# OLED_V3_1.net
KiCad netlist of a schematic drawn in Altium Designer
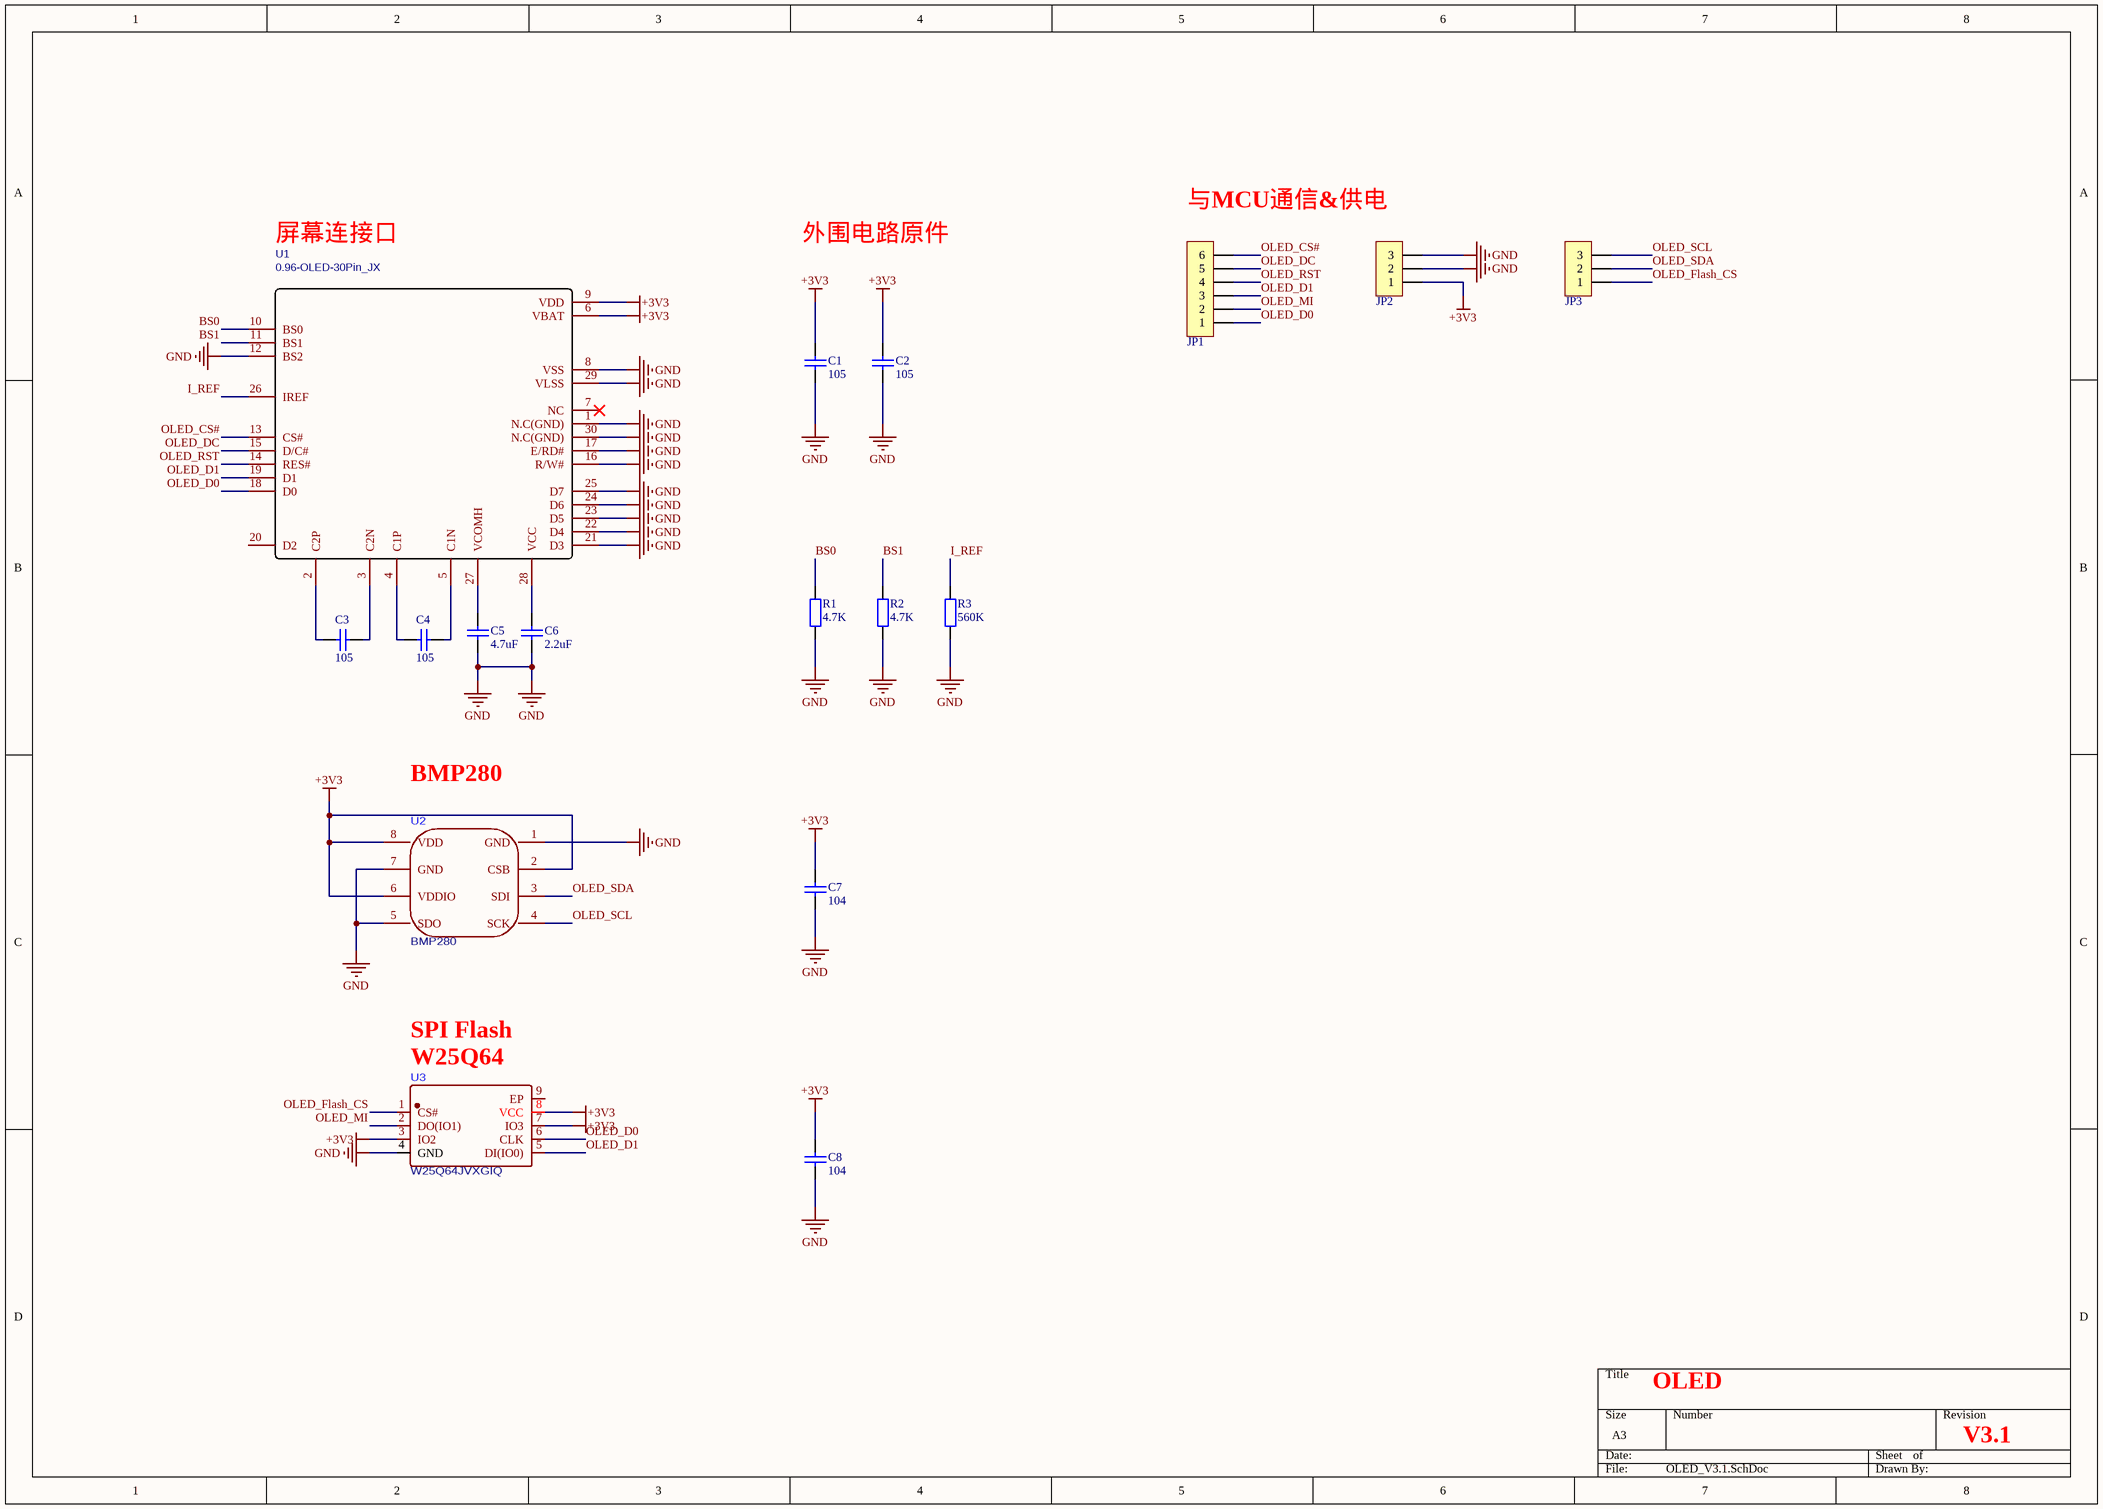
[diagram p0: OLED_V3.1.SchDoc]

(export (version "E")
  (design (tool "Eeschema 10.0.6"))
  (components
    (comp (ref "C1")
      (value "105")
      (footprint "C0603_M")
      (description "贴片电容/MLCC电容")
      (libsource (lib "R-L-C-FUSE-XTAL-FB-RX") (part "C"))
    )
    (comp (ref "C2")
      (value "105")
      (footprint "C0603_M")
      (description "贴片电容/MLCC电容")
      (libsource (lib "R-L-C-FUSE-XTAL-FB-RX") (part "C"))
    )
    (comp (ref "C3")
      (value "105")
      (footprint "C0603_M")
      (description "贴片电容/MLCC电容")
      (libsource (lib "R-L-C-FUSE-XTAL-FB-RX") (part "C"))
    )
    (comp (ref "C4")
      (value "105")
      (footprint "C0603_M")
      (description "贴片电容/MLCC电容")
      (libsource (lib "R-L-C-FUSE-XTAL-FB-RX") (part "C"))
    )
    (comp (ref "C5")
      (value "4.7uF")
      (footprint "C0603_M")
      (description "贴片电容/MLCC电容")
      (libsource (lib "R-L-C-FUSE-XTAL-FB-RX") (part "C"))
    )
    (comp (ref "C6")
      (value "2.2uF")
      (footprint "C0603_M")
      (description "贴片电容/MLCC电容")
      (libsource (lib "R-L-C-FUSE-XTAL-FB-RX") (part "C"))
    )
    (comp (ref "C7")
      (value "104")
      (footprint "C0603_M")
      (description "贴片电容/MLCC电容")
      (libsource (lib "R-L-C-FUSE-XTAL-FB-RX") (part "C"))
    )
    (comp (ref "C8")
      (value "104")
      (footprint "C0603_M")
      (description "贴片电容/MLCC电容")
      (libsource (lib "R-L-C-FUSE-XTAL-FB-RX") (part "C"))
    )
    (comp (ref "JP1")
      (value "HDR-1X6")
      (footprint "HDR-1X6")
      (description "6P接插件")
      (fields (field (name "版权归属") "黎明电子style"))
      (libsource (lib "接插件") (part "Header 6"))
    )
    (comp (ref "JP2")
      (value "HDR-1X3")
      (footprint "OLED_3PIN")
      (description "3P接插件")
      (fields (field (name "版权归属") "黎明电子style"))
      (libsource (lib "接插件") (part "Header 3"))
    )
    (comp (ref "JP3")
      (value "HDR-1X3")
      (footprint "OLED_3PIN")
      (description "3P接插件")
      (fields (field (name "版权归属") "黎明电子style"))
      (libsource (lib "接插件") (part "Header 3"))
    )
    (comp (ref "R1")
      (value "4.7K")
      (footprint "R0603_M")
      (description "贴片电阻")
      (libsource (lib "R-L-C-FUSE-XTAL-FB-RX") (part "R"))
    )
    (comp (ref "R2")
      (value "4.7K")
      (footprint "R0603_M")
      (description "贴片电阻")
      (libsource (lib "R-L-C-FUSE-XTAL-FB-RX") (part "R"))
    )
    (comp (ref "R3")
      (value "560K")
      (footprint "R0603_M")
      (description "贴片电阻")
      (libsource (lib "R-L-C-FUSE-XTAL-FB-RX") (part "R"))
    )
    (comp (ref "U1")
      (value "0.96-OLED-30Pin_JX")
      (footprint "SSD1306-30PIN_JX")
      (libsource (lib "Schlib1") (part "0.96-OLED-30Pin_JX"))
    )
    (comp (ref "U2")
      (value "BMP280")
      (footprint "LGA-8_L2.5-W2.0-P0.65_AMP6127")
      (libsource (lib "Schlib1") (part "BMP280"))
    )
    (comp (ref "U3")
      (value "W25Q64JVXGIQ")
      (footprint "XSON-8_L4.0-W4.0-P0.80-TL-EP")
      (libsource (lib "Schlib1") (part "W25Q64JVXGIQ"))
    )
  )
  (nets
    (net (code "1") (name "+3V3") (class "Default")
      (node (ref "C1") (pin "2") (pinfunction "2_2") (pintype "passive"))
      (node (ref "C2") (pin "2") (pinfunction "2_2") (pintype "passive"))
      (node (ref "C7") (pin "2") (pinfunction "2_2") (pintype "passive"))
      (node (ref "C8") (pin "2") (pinfunction "2_2") (pintype "passive"))
      (node (ref "JP2") (pin "1") (pinfunction "1_1") (pintype "passive"))
      (node (ref "U1") (pin "6") (pinfunction "VBAT_6") (pintype "passive"))
      (node (ref "U1") (pin "9") (pinfunction "VDD_9") (pintype "passive"))
      (node (ref "U2") (pin "2") (pinfunction "CSB_2") (pintype "passive"))
      (node (ref "U2") (pin "6") (pinfunction "VDDIO_6") (pintype "passive"))
      (node (ref "U2") (pin "8") (pinfunction "VDD_8") (pintype "passive"))
      (node (ref "U3") (pin "3") (pinfunction "IO2_3") (pintype "passive"))
      (node (ref "U3") (pin "7") (pinfunction "IO3_7") (pintype "passive"))
      (node (ref "U3") (pin "8") (pinfunction "VCC_8") (pintype "passive"))
    )
    (net (code "2") (name "/BS0") (class "Default")
      (node (ref "R1") (pin "2") (pinfunction "2_2") (pintype "passive"))
      (node (ref "U1") (pin "10") (pinfunction "BS0_10") (pintype "passive"))
    )
    (net (code "3") (name "/BS1") (class "Default")
      (node (ref "R2") (pin "2") (pinfunction "2_2") (pintype "passive"))
      (node (ref "U1") (pin "11") (pinfunction "BS1_11") (pintype "passive"))
    )
    (net (code "4") (name "/I_REF") (class "Default")
      (node (ref "R3") (pin "2") (pinfunction "2_2") (pintype "passive"))
      (node (ref "U1") (pin "26") (pinfunction "IREF_26") (pintype "passive"))
    )
    (net (code "5") (name "/OLED_CS#") (class "Default")
      (node (ref "JP1") (pin "6") (pinfunction "6_6") (pintype "passive"))
      (node (ref "U1") (pin "13") (pinfunction "CS#_13") (pintype "passive"))
    )
    (net (code "6") (name "/OLED_D0") (class "Default")
      (node (ref "JP1") (pin "1") (pinfunction "1_1") (pintype "passive"))
      (node (ref "U1") (pin "18") (pinfunction "D0_18") (pintype "passive"))
      (node (ref "U3") (pin "6") (pinfunction "CLK_6") (pintype "passive"))
    )
    (net (code "7") (name "/OLED_D1") (class "Default")
      (node (ref "JP1") (pin "3") (pinfunction "3_3") (pintype "passive"))
      (node (ref "U1") (pin "19") (pinfunction "D1_19") (pintype "passive"))
      (node (ref "U3") (pin "5") (pinfunction "DI(IO0)_5") (pintype "passive"))
    )
    (net (code "8") (name "/OLED_DC") (class "Default")
      (node (ref "JP1") (pin "5") (pinfunction "5_5") (pintype "passive"))
      (node (ref "U1") (pin "15") (pinfunction "D/C#_15") (pintype "passive"))
    )
    (net (code "9") (name "/OLED_Flash_CS") (class "Default")
      (node (ref "JP3") (pin "1") (pinfunction "1_1") (pintype "passive"))
      (node (ref "U3") (pin "1") (pinfunction "CS#_1") (pintype "passive"))
    )
    (net (code "10") (name "/OLED_MI") (class "Default")
      (node (ref "JP1") (pin "2") (pinfunction "2_2") (pintype "passive"))
      (node (ref "U3") (pin "2") (pinfunction "DO(IO1)_2") (pintype "passive"))
    )
    (net (code "11") (name "/OLED_RST") (class "Default")
      (node (ref "JP1") (pin "4") (pinfunction "4_4") (pintype "passive"))
      (node (ref "U1") (pin "14") (pinfunction "RES#_14") (pintype "passive"))
    )
    (net (code "12") (name "/OLED_SCL") (class "Default")
      (node (ref "JP3") (pin "3") (pinfunction "3_3") (pintype "passive"))
      (node (ref "U2") (pin "4") (pinfunction "SCK_4") (pintype "passive"))
    )
    (net (code "13") (name "/OLED_SDA") (class "Default")
      (node (ref "JP3") (pin "2") (pinfunction "2_2") (pintype "passive"))
      (node (ref "U2") (pin "3") (pinfunction "SDI_3") (pintype "passive"))
    )
    (net (code "14") (name "GND") (class "Default")
      (node (ref "C1") (pin "1") (pinfunction "1_1") (pintype "passive"))
      (node (ref "C2") (pin "1") (pinfunction "1_1") (pintype "passive"))
      (node (ref "C5") (pin "1") (pinfunction "1_1") (pintype "passive"))
      (node (ref "C6") (pin "1") (pinfunction "1_1") (pintype "passive"))
      (node (ref "C7") (pin "1") (pinfunction "1_1") (pintype "passive"))
      (node (ref "C8") (pin "1") (pinfunction "1_1") (pintype "passive"))
      (node (ref "JP2") (pin "2") (pinfunction "2_2") (pintype "passive"))
      (node (ref "JP2") (pin "3") (pinfunction "3_3") (pintype "passive"))
      (node (ref "R1") (pin "1") (pinfunction "1_1") (pintype "passive"))
      (node (ref "R2") (pin "1") (pinfunction "1_1") (pintype "passive"))
      (node (ref "R3") (pin "1") (pinfunction "1_1") (pintype "passive"))
      (node (ref "U1") (pin "1") (pinfunction "N.C(GND)_1") (pintype "passive"))
      (node (ref "U1") (pin "12") (pinfunction "BS2_12") (pintype "passive"))
      (node (ref "U1") (pin "16") (pinfunction "R/W#_16") (pintype "passive"))
      (node (ref "U1") (pin "17") (pinfunction "E/RD#_17") (pintype "passive"))
      (node (ref "U1") (pin "21") (pinfunction "D3_21") (pintype "passive"))
      (node (ref "U1") (pin "22") (pinfunction "D4_22") (pintype "passive"))
      (node (ref "U1") (pin "23") (pinfunction "D5_23") (pintype "passive"))
      (node (ref "U1") (pin "24") (pinfunction "D6_24") (pintype "passive"))
      (node (ref "U1") (pin "25") (pinfunction "D7_25") (pintype "passive"))
      (node (ref "U1") (pin "29") (pinfunction "VLSS_29") (pintype "passive"))
      (node (ref "U1") (pin "30") (pinfunction "N.C(GND)_30") (pintype "passive"))
      (node (ref "U1") (pin "8") (pinfunction "VSS_8") (pintype "passive"))
      (node (ref "U2") (pin "1") (pinfunction "GND_1") (pintype "passive"))
      (node (ref "U2") (pin "5") (pinfunction "SDO_5") (pintype "passive"))
      (node (ref "U2") (pin "7") (pinfunction "GND_7") (pintype "passive"))
      (node (ref "U3") (pin "4") (pinfunction "GND_4") (pintype "passive"))
    )
    (net (code "15") (name "Net-(U1-C1N)") (class "Default")
      (node (ref "C4") (pin "1") (pinfunction "1_1") (pintype "passive"))
      (node (ref "U1") (pin "5") (pinfunction "C1N_5") (pintype "passive"))
    )
    (net (code "16") (name "Net-(U1-C1P)") (class "Default")
      (node (ref "C4") (pin "2") (pinfunction "2_2") (pintype "passive"))
      (node (ref "U1") (pin "4") (pinfunction "C1P_4") (pintype "passive"))
    )
    (net (code "17") (name "Net-(U1-C2N)") (class "Default")
      (node (ref "C3") (pin "1") (pinfunction "1_1") (pintype "passive"))
      (node (ref "U1") (pin "3") (pinfunction "C2N_3") (pintype "passive"))
    )
    (net (code "18") (name "Net-(U1-C2P)") (class "Default")
      (node (ref "C3") (pin "2") (pinfunction "2_2") (pintype "passive"))
      (node (ref "U1") (pin "2") (pinfunction "C2P_2") (pintype "passive"))
    )
    (net (code "19") (name "Net-(U1-VCC)") (class "Default")
      (node (ref "C6") (pin "2") (pinfunction "2_2") (pintype "passive"))
      (node (ref "U1") (pin "28") (pinfunction "VCC_28") (pintype "passive"))
    )
    (net (code "20") (name "Net-(U1-VCOMH)") (class "Default")
      (node (ref "C5") (pin "2") (pinfunction "2_2") (pintype "passive"))
      (node (ref "U1") (pin "27") (pinfunction "VCOMH_27") (pintype "passive"))
    )
    (net (code "21") (name "unconnected-(U1-D2-Pad20)") (class "Default")
      (node (ref "U1") (pin "20") (pinfunction "D2_20") (pintype "passive"))
    )
    (net (code "22") (name "unconnected-(U1-NC-Pad7)") (class "Default")
      (node (ref "U1") (pin "7") (pinfunction "NC_7") (pintype "passive+no_connect"))
    )
    (net (code "23") (name "unconnected-(U3-EP-Pad9)") (class "Default")
      (node (ref "U3") (pin "9") (pinfunction "EP_9") (pintype "passive"))
    )
  )
)
